# AMS_Enerdel_Adapter_rev7.net
KiCad netlist of a schematic drawn in EAGLE
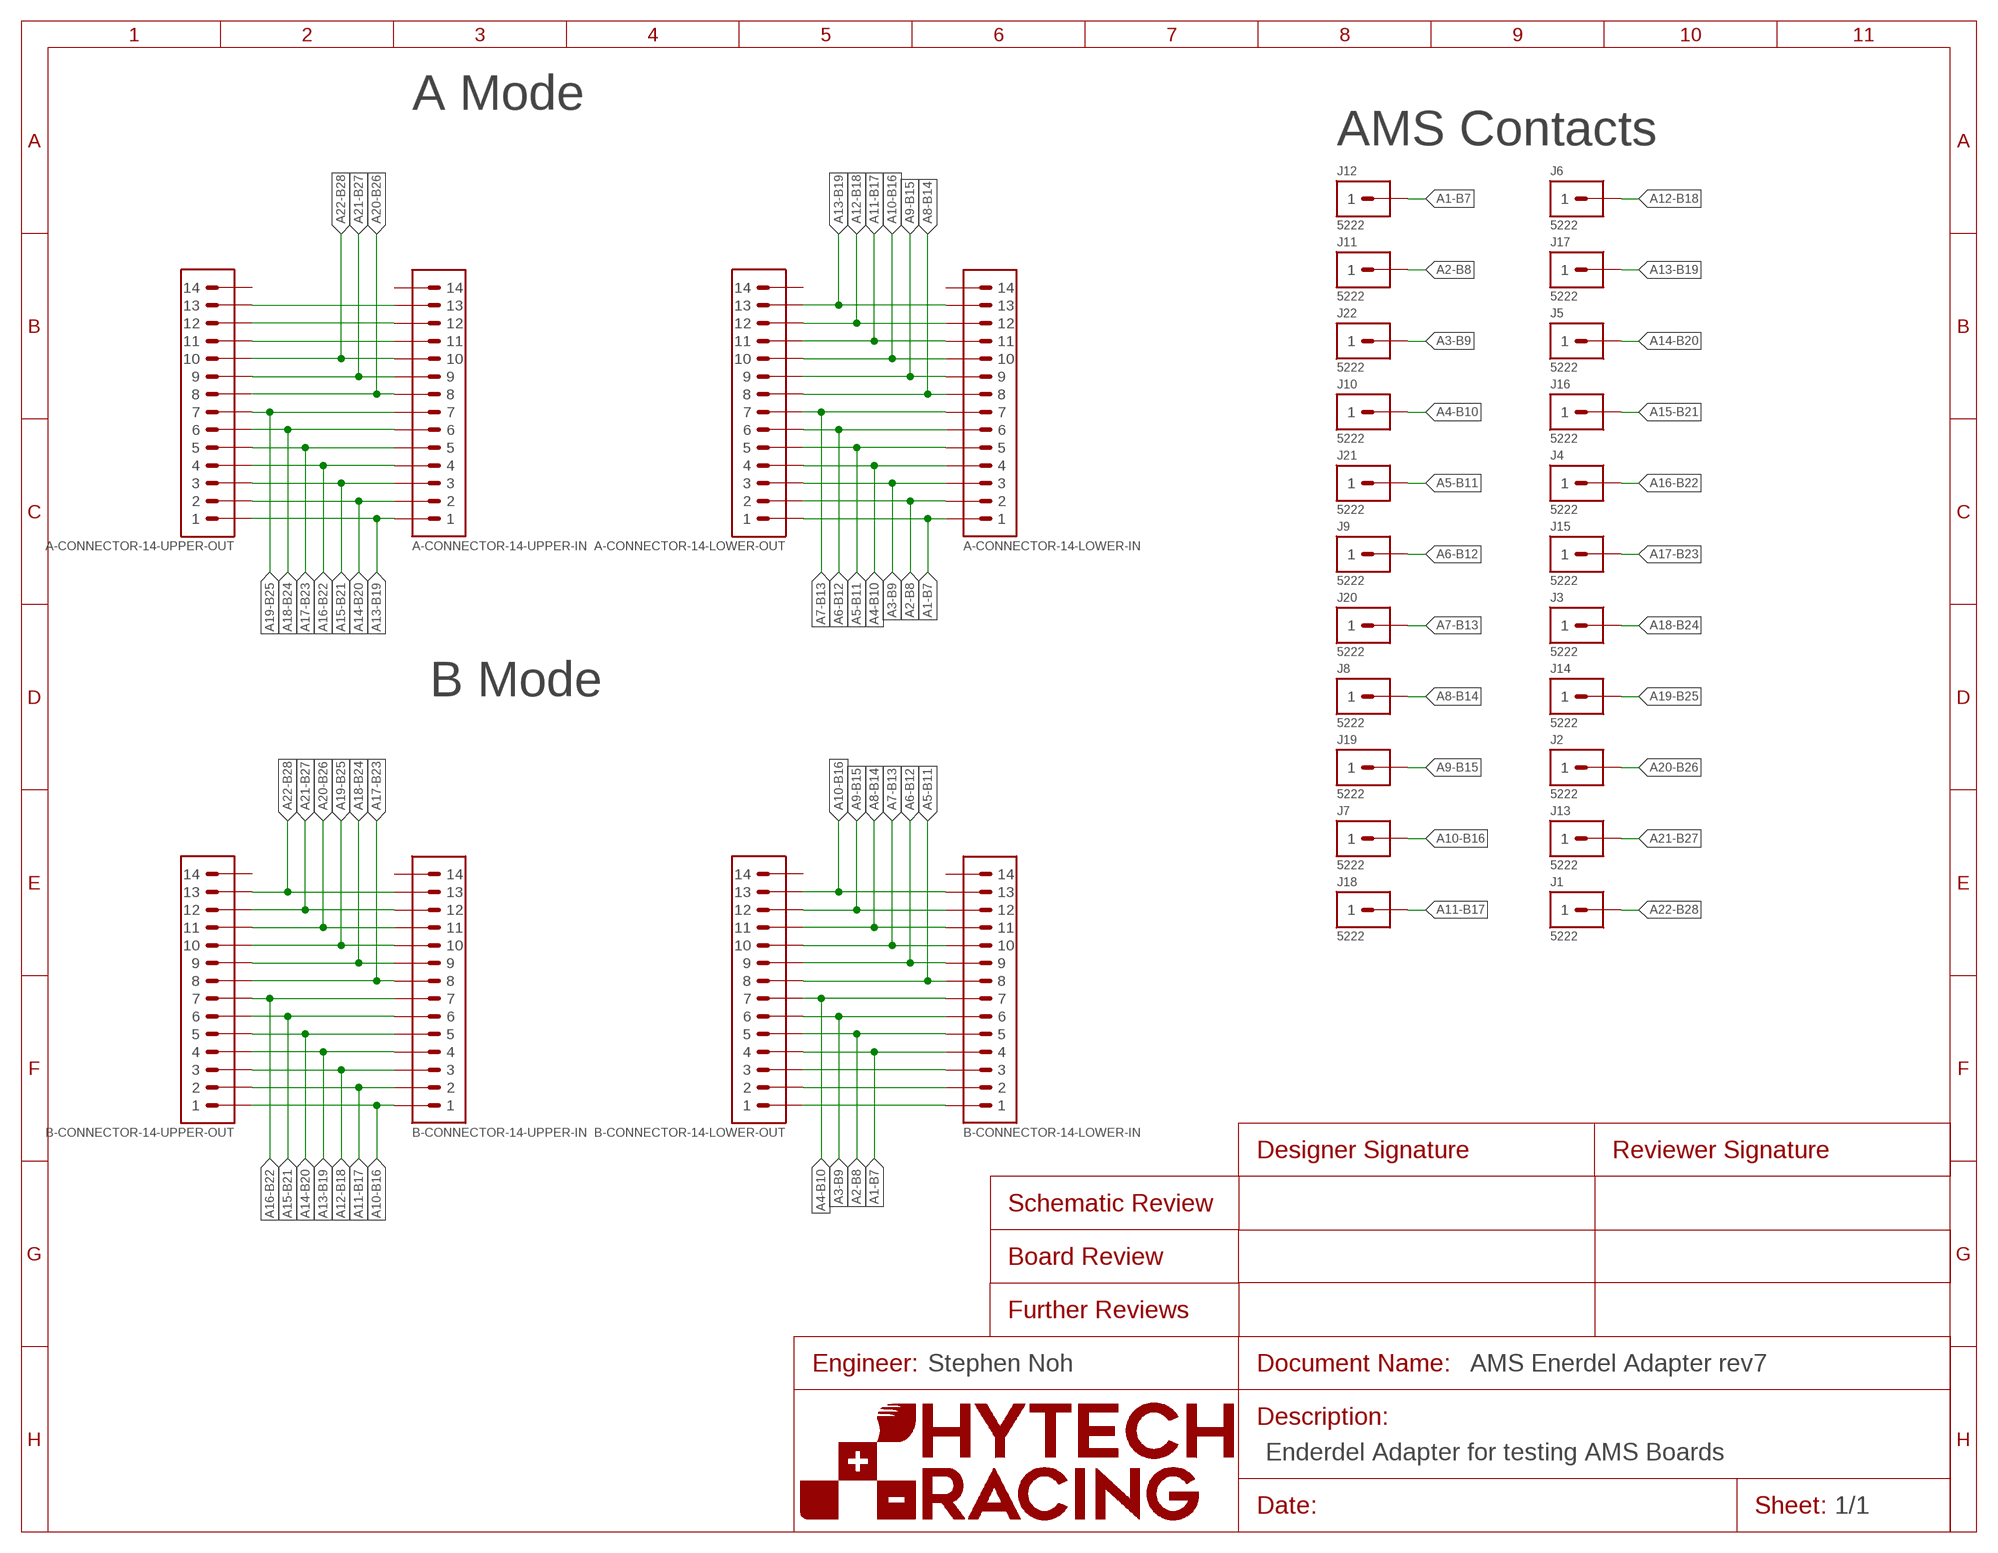
[diagram p0: schematic, sheet 1]

(export (version "E")
  (design (tool "Eeschema 10.0.6"))
  (components
    (comp (ref "A-CONNECTOR-14-LOWER-IN")
      (value "CONNECTOR-14_MINIFIT_")
      (footprint "eagle-import:MOLEX_MINIFIT_PTH_14")
      (libsource (lib "eagle-import") (part "CONNECTOR-14_?_MINIFIT"))
    )
    (comp (ref "A-CONNECTOR-14-LOWER-OUT")
      (value "CONNECTOR-14_MINIFIT_")
      (footprint "eagle-import:MOLEX_MINIFIT_PTH_14")
      (libsource (lib "eagle-import") (part "CONNECTOR-14_?_MINIFIT"))
    )
    (comp (ref "A-CONNECTOR-14-UPPER-IN")
      (value "CONNECTOR-14_NANOFIT_")
      (footprint "eagle-import:MOLEX_NANOFIT_PTH_14")
      (libsource (lib "eagle-import") (part "CONNECTOR-14_?_NANOFIT"))
    )
    (comp (ref "A-CONNECTOR-14-UPPER-OUT")
      (value "CONNECTOR-14_NANOFIT_")
      (footprint "eagle-import:MOLEX_NANOFIT_PTH_14")
      (libsource (lib "eagle-import") (part "CONNECTOR-14_?_NANOFIT"))
    )
    (comp (ref "B-CONNECTOR-14-LOWER-IN")
      (value "CONNECTOR-14_MINIFIT_")
      (footprint "eagle-import:MOLEX_MINIFIT_PTH_14")
      (libsource (lib "eagle-import") (part "CONNECTOR-14_?_MINIFIT"))
    )
    (comp (ref "B-CONNECTOR-14-LOWER-OUT")
      (value "CONNECTOR-14_MINIFIT_")
      (footprint "eagle-import:MOLEX_MINIFIT_PTH_14")
      (libsource (lib "eagle-import") (part "CONNECTOR-14_?_MINIFIT"))
    )
    (comp (ref "B-CONNECTOR-14-UPPER-IN")
      (value "CONNECTOR-14_NANOFIT_")
      (footprint "eagle-import:MOLEX_NANOFIT_PTH_14")
      (libsource (lib "eagle-import") (part "CONNECTOR-14_?_NANOFIT"))
    )
    (comp (ref "B-CONNECTOR-14-UPPER-OUT")
      (value "CONNECTOR-14_NANOFIT_")
      (footprint "eagle-import:MOLEX_NANOFIT_PTH_14")
      (libsource (lib "eagle-import") (part "CONNECTOR-14_?_NANOFIT"))
    )
    (comp (ref "J1")
      (value "CONNECTOR-1_5222_")
      (footprint "eagle-import:5222")
      (fields (field (name "MPN") "5222") (field (name "MANUFACTURER") "Keystone Electronics"))
      (libsource (lib "eagle-import") (part "CONNECTOR-1_?_5222"))
    )
    (comp (ref "J2")
      (value "CONNECTOR-1_5222_")
      (footprint "eagle-import:5222")
      (fields (field (name "MPN") "5222") (field (name "MANUFACTURER") "Keystone Electronics"))
      (libsource (lib "eagle-import") (part "CONNECTOR-1_?_5222"))
    )
    (comp (ref "J3")
      (value "CONNECTOR-1_5222_")
      (footprint "eagle-import:5222")
      (fields (field (name "MPN") "5222") (field (name "MANUFACTURER") "Keystone Electronics"))
      (libsource (lib "eagle-import") (part "CONNECTOR-1_?_5222"))
    )
    (comp (ref "J4")
      (value "CONNECTOR-1_5222_")
      (footprint "eagle-import:5222")
      (fields (field (name "MPN") "5222") (field (name "MANUFACTURER") "Keystone Electronics"))
      (libsource (lib "eagle-import") (part "CONNECTOR-1_?_5222"))
    )
    (comp (ref "J5")
      (value "CONNECTOR-1_5222_")
      (footprint "eagle-import:5222")
      (fields (field (name "MPN") "5222") (field (name "MANUFACTURER") "Keystone Electronics"))
      (libsource (lib "eagle-import") (part "CONNECTOR-1_?_5222"))
    )
    (comp (ref "J6")
      (value "CONNECTOR-1_5222_")
      (footprint "eagle-import:5222")
      (fields (field (name "MPN") "5222") (field (name "MANUFACTURER") "Keystone Electronics"))
      (libsource (lib "eagle-import") (part "CONNECTOR-1_?_5222"))
    )
    (comp (ref "J7")
      (value "CONNECTOR-1_5222_")
      (footprint "eagle-import:5222")
      (fields (field (name "MPN") "5222") (field (name "MANUFACTURER") "Keystone Electronics"))
      (libsource (lib "eagle-import") (part "CONNECTOR-1_?_5222"))
    )
    (comp (ref "J8")
      (value "CONNECTOR-1_5222_")
      (footprint "eagle-import:5222")
      (fields (field (name "MPN") "5222") (field (name "MANUFACTURER") "Keystone Electronics"))
      (libsource (lib "eagle-import") (part "CONNECTOR-1_?_5222"))
    )
    (comp (ref "J9")
      (value "CONNECTOR-1_5222_")
      (footprint "eagle-import:5222")
      (fields (field (name "MPN") "5222") (field (name "MANUFACTURER") "Keystone Electronics"))
      (libsource (lib "eagle-import") (part "CONNECTOR-1_?_5222"))
    )
    (comp (ref "J10")
      (value "CONNECTOR-1_5222_")
      (footprint "eagle-import:5222")
      (fields (field (name "MPN") "5222") (field (name "MANUFACTURER") "Keystone Electronics"))
      (libsource (lib "eagle-import") (part "CONNECTOR-1_?_5222"))
    )
    (comp (ref "J11")
      (value "CONNECTOR-1_5222_")
      (footprint "eagle-import:5222")
      (fields (field (name "MPN") "5222") (field (name "MANUFACTURER") "Keystone Electronics"))
      (libsource (lib "eagle-import") (part "CONNECTOR-1_?_5222"))
    )
    (comp (ref "J12")
      (value "CONNECTOR-1_5222_")
      (footprint "eagle-import:5222")
      (fields (field (name "MPN") "5222") (field (name "MANUFACTURER") "Keystone Electronics"))
      (libsource (lib "eagle-import") (part "CONNECTOR-1_?_5222"))
    )
    (comp (ref "J13")
      (value "CONNECTOR-1_5222_")
      (footprint "eagle-import:5222")
      (fields (field (name "MPN") "5222") (field (name "MANUFACTURER") "Keystone Electronics"))
      (libsource (lib "eagle-import") (part "CONNECTOR-1_?_5222"))
    )
    (comp (ref "J14")
      (value "CONNECTOR-1_5222_")
      (footprint "eagle-import:5222")
      (fields (field (name "MPN") "5222") (field (name "MANUFACTURER") "Keystone Electronics"))
      (libsource (lib "eagle-import") (part "CONNECTOR-1_?_5222"))
    )
    (comp (ref "J15")
      (value "CONNECTOR-1_5222_")
      (footprint "eagle-import:5222")
      (fields (field (name "MPN") "5222") (field (name "MANUFACTURER") "Keystone Electronics"))
      (libsource (lib "eagle-import") (part "CONNECTOR-1_?_5222"))
    )
    (comp (ref "J16")
      (value "CONNECTOR-1_5222_")
      (footprint "eagle-import:5222")
      (fields (field (name "MPN") "5222") (field (name "MANUFACTURER") "Keystone Electronics"))
      (libsource (lib "eagle-import") (part "CONNECTOR-1_?_5222"))
    )
    (comp (ref "J17")
      (value "CONNECTOR-1_5222_")
      (footprint "eagle-import:5222")
      (fields (field (name "MPN") "5222") (field (name "MANUFACTURER") "Keystone Electronics"))
      (libsource (lib "eagle-import") (part "CONNECTOR-1_?_5222"))
    )
    (comp (ref "J18")
      (value "CONNECTOR-1_5222_")
      (footprint "eagle-import:5222")
      (fields (field (name "MPN") "5222") (field (name "MANUFACTURER") "Keystone Electronics"))
      (libsource (lib "eagle-import") (part "CONNECTOR-1_?_5222"))
    )
    (comp (ref "J19")
      (value "CONNECTOR-1_5222_")
      (footprint "eagle-import:5222")
      (fields (field (name "MPN") "5222") (field (name "MANUFACTURER") "Keystone Electronics"))
      (libsource (lib "eagle-import") (part "CONNECTOR-1_?_5222"))
    )
    (comp (ref "J20")
      (value "CONNECTOR-1_5222_")
      (footprint "eagle-import:5222")
      (fields (field (name "MPN") "5222") (field (name "MANUFACTURER") "Keystone Electronics"))
      (libsource (lib "eagle-import") (part "CONNECTOR-1_?_5222"))
    )
    (comp (ref "J21")
      (value "CONNECTOR-1_5222_")
      (footprint "eagle-import:5222")
      (fields (field (name "MPN") "5222") (field (name "MANUFACTURER") "Keystone Electronics"))
      (libsource (lib "eagle-import") (part "CONNECTOR-1_?_5222"))
    )
    (comp (ref "J22")
      (value "CONNECTOR-1_5222_")
      (footprint "eagle-import:5222")
      (fields (field (name "MPN") "5222") (field (name "MANUFACTURER") "Keystone Electronics"))
      (libsource (lib "eagle-import") (part "CONNECTOR-1_?_5222"))
    )
  )
  (nets
    (net (code "1") (name "A1-B7") (class "Default")
      (node (ref "A-CONNECTOR-14-LOWER-IN") (pin "1") (pinfunction "1_1") (pintype "passive"))
      (node (ref "A-CONNECTOR-14-LOWER-OUT") (pin "1") (pinfunction "1_1") (pintype "passive"))
      (node (ref "B-CONNECTOR-14-LOWER-IN") (pin "4") (pinfunction "4_4") (pintype "passive"))
      (node (ref "B-CONNECTOR-14-LOWER-OUT") (pin "4") (pinfunction "4_4") (pintype "passive"))
      (node (ref "J12") (pin "1") (pinfunction "1_1") (pintype "passive"))
    )
    (net (code "2") (name "A2-B8") (class "Default")
      (node (ref "A-CONNECTOR-14-LOWER-IN") (pin "2") (pinfunction "2_2") (pintype "passive"))
      (node (ref "A-CONNECTOR-14-LOWER-OUT") (pin "2") (pinfunction "2_2") (pintype "passive"))
      (node (ref "B-CONNECTOR-14-LOWER-IN") (pin "5") (pinfunction "5_5") (pintype "passive"))
      (node (ref "B-CONNECTOR-14-LOWER-OUT") (pin "5") (pinfunction "5_5") (pintype "passive"))
      (node (ref "J11") (pin "1") (pinfunction "1_1") (pintype "passive"))
    )
    (net (code "3") (name "A3-B9") (class "Default")
      (node (ref "A-CONNECTOR-14-LOWER-IN") (pin "3") (pinfunction "3_3") (pintype "passive"))
      (node (ref "A-CONNECTOR-14-LOWER-OUT") (pin "3") (pinfunction "3_3") (pintype "passive"))
      (node (ref "B-CONNECTOR-14-LOWER-IN") (pin "6") (pinfunction "6_6") (pintype "passive"))
      (node (ref "B-CONNECTOR-14-LOWER-OUT") (pin "6") (pinfunction "6_6") (pintype "passive"))
      (node (ref "J22") (pin "1") (pinfunction "1_1") (pintype "passive"))
    )
    (net (code "4") (name "A4-B10") (class "Default")
      (node (ref "A-CONNECTOR-14-LOWER-IN") (pin "4") (pinfunction "4_4") (pintype "passive"))
      (node (ref "A-CONNECTOR-14-LOWER-OUT") (pin "4") (pinfunction "4_4") (pintype "passive"))
      (node (ref "B-CONNECTOR-14-LOWER-IN") (pin "7") (pinfunction "7_7") (pintype "passive"))
      (node (ref "B-CONNECTOR-14-LOWER-OUT") (pin "7") (pinfunction "7_7") (pintype "passive"))
      (node (ref "J10") (pin "1") (pinfunction "1_1") (pintype "passive"))
    )
    (net (code "5") (name "A5-B11") (class "Default")
      (node (ref "A-CONNECTOR-14-LOWER-IN") (pin "5") (pinfunction "5_5") (pintype "passive"))
      (node (ref "A-CONNECTOR-14-LOWER-OUT") (pin "5") (pinfunction "5_5") (pintype "passive"))
      (node (ref "B-CONNECTOR-14-LOWER-IN") (pin "8") (pinfunction "8_8") (pintype "passive"))
      (node (ref "B-CONNECTOR-14-LOWER-OUT") (pin "8") (pinfunction "8_8") (pintype "passive"))
      (node (ref "J21") (pin "1") (pinfunction "1_1") (pintype "passive"))
    )
    (net (code "6") (name "A6-B12") (class "Default")
      (node (ref "A-CONNECTOR-14-LOWER-IN") (pin "6") (pinfunction "6_6") (pintype "passive"))
      (node (ref "A-CONNECTOR-14-LOWER-OUT") (pin "6") (pinfunction "6_6") (pintype "passive"))
      (node (ref "B-CONNECTOR-14-LOWER-IN") (pin "9") (pinfunction "9_9") (pintype "passive"))
      (node (ref "B-CONNECTOR-14-LOWER-OUT") (pin "9") (pinfunction "9_9") (pintype "passive"))
      (node (ref "J9") (pin "1") (pinfunction "1_1") (pintype "passive"))
    )
    (net (code "7") (name "A7-B13") (class "Default")
      (node (ref "A-CONNECTOR-14-LOWER-IN") (pin "7") (pinfunction "7_7") (pintype "passive"))
      (node (ref "A-CONNECTOR-14-LOWER-OUT") (pin "7") (pinfunction "7_7") (pintype "passive"))
      (node (ref "B-CONNECTOR-14-LOWER-IN") (pin "10") (pinfunction "10_10") (pintype "passive"))
      (node (ref "B-CONNECTOR-14-LOWER-OUT") (pin "10") (pinfunction "10_10") (pintype "passive"))
      (node (ref "J20") (pin "1") (pinfunction "1_1") (pintype "passive"))
    )
    (net (code "8") (name "A8-B14") (class "Default")
      (node (ref "A-CONNECTOR-14-LOWER-IN") (pin "8") (pinfunction "8_8") (pintype "passive"))
      (node (ref "A-CONNECTOR-14-LOWER-OUT") (pin "8") (pinfunction "8_8") (pintype "passive"))
      (node (ref "B-CONNECTOR-14-LOWER-IN") (pin "11") (pinfunction "11_11") (pintype "passive"))
      (node (ref "B-CONNECTOR-14-LOWER-OUT") (pin "11") (pinfunction "11_11") (pintype "passive"))
      (node (ref "J8") (pin "1") (pinfunction "1_1") (pintype "passive"))
    )
    (net (code "9") (name "A9-B15") (class "Default")
      (node (ref "A-CONNECTOR-14-LOWER-IN") (pin "9") (pinfunction "9_9") (pintype "passive"))
      (node (ref "A-CONNECTOR-14-LOWER-OUT") (pin "9") (pinfunction "9_9") (pintype "passive"))
      (node (ref "B-CONNECTOR-14-LOWER-IN") (pin "12") (pinfunction "12_12") (pintype "passive"))
      (node (ref "B-CONNECTOR-14-LOWER-OUT") (pin "12") (pinfunction "12_12") (pintype "passive"))
      (node (ref "J19") (pin "1") (pinfunction "1_1") (pintype "passive"))
    )
    (net (code "10") (name "A10-B16") (class "Default")
      (node (ref "A-CONNECTOR-14-LOWER-IN") (pin "10") (pinfunction "10_10") (pintype "passive"))
      (node (ref "A-CONNECTOR-14-LOWER-OUT") (pin "10") (pinfunction "10_10") (pintype "passive"))
      (node (ref "B-CONNECTOR-14-LOWER-IN") (pin "13") (pinfunction "13_13") (pintype "passive"))
      (node (ref "B-CONNECTOR-14-LOWER-OUT") (pin "13") (pinfunction "13_13") (pintype "passive"))
      (node (ref "B-CONNECTOR-14-UPPER-IN") (pin "1") (pinfunction "1_1") (pintype "passive"))
      (node (ref "B-CONNECTOR-14-UPPER-OUT") (pin "1") (pinfunction "1_1") (pintype "passive"))
      (node (ref "J7") (pin "1") (pinfunction "1_1") (pintype "passive"))
    )
    (net (code "11") (name "A11-B17") (class "Default")
      (node (ref "A-CONNECTOR-14-LOWER-IN") (pin "11") (pinfunction "11_11") (pintype "passive"))
      (node (ref "A-CONNECTOR-14-LOWER-OUT") (pin "11") (pinfunction "11_11") (pintype "passive"))
      (node (ref "B-CONNECTOR-14-UPPER-IN") (pin "2") (pinfunction "2_2") (pintype "passive"))
      (node (ref "B-CONNECTOR-14-UPPER-OUT") (pin "2") (pinfunction "2_2") (pintype "passive"))
      (node (ref "J18") (pin "1") (pinfunction "1_1") (pintype "passive"))
    )
    (net (code "12") (name "A12-B18") (class "Default")
      (node (ref "A-CONNECTOR-14-LOWER-IN") (pin "12") (pinfunction "12_12") (pintype "passive"))
      (node (ref "A-CONNECTOR-14-LOWER-OUT") (pin "12") (pinfunction "12_12") (pintype "passive"))
      (node (ref "B-CONNECTOR-14-UPPER-IN") (pin "3") (pinfunction "3_3") (pintype "passive"))
      (node (ref "B-CONNECTOR-14-UPPER-OUT") (pin "3") (pinfunction "3_3") (pintype "passive"))
      (node (ref "J6") (pin "1") (pinfunction "1_1") (pintype "passive"))
    )
    (net (code "13") (name "A13-B19") (class "Default")
      (node (ref "A-CONNECTOR-14-LOWER-IN") (pin "13") (pinfunction "13_13") (pintype "passive"))
      (node (ref "A-CONNECTOR-14-LOWER-OUT") (pin "13") (pinfunction "13_13") (pintype "passive"))
      (node (ref "A-CONNECTOR-14-UPPER-IN") (pin "1") (pinfunction "1_1") (pintype "passive"))
      (node (ref "A-CONNECTOR-14-UPPER-OUT") (pin "1") (pinfunction "1_1") (pintype "passive"))
      (node (ref "B-CONNECTOR-14-UPPER-IN") (pin "4") (pinfunction "4_4") (pintype "passive"))
      (node (ref "B-CONNECTOR-14-UPPER-OUT") (pin "4") (pinfunction "4_4") (pintype "passive"))
      (node (ref "J17") (pin "1") (pinfunction "1_1") (pintype "passive"))
    )
    (net (code "14") (name "A14-B20") (class "Default")
      (node (ref "A-CONNECTOR-14-UPPER-IN") (pin "2") (pinfunction "2_2") (pintype "passive"))
      (node (ref "A-CONNECTOR-14-UPPER-OUT") (pin "2") (pinfunction "2_2") (pintype "passive"))
      (node (ref "B-CONNECTOR-14-UPPER-IN") (pin "5") (pinfunction "5_5") (pintype "passive"))
      (node (ref "B-CONNECTOR-14-UPPER-OUT") (pin "5") (pinfunction "5_5") (pintype "passive"))
      (node (ref "J5") (pin "1") (pinfunction "1_1") (pintype "passive"))
    )
    (net (code "15") (name "A15-B21") (class "Default")
      (node (ref "A-CONNECTOR-14-UPPER-IN") (pin "3") (pinfunction "3_3") (pintype "passive"))
      (node (ref "A-CONNECTOR-14-UPPER-OUT") (pin "3") (pinfunction "3_3") (pintype "passive"))
      (node (ref "B-CONNECTOR-14-UPPER-IN") (pin "6") (pinfunction "6_6") (pintype "passive"))
      (node (ref "B-CONNECTOR-14-UPPER-OUT") (pin "6") (pinfunction "6_6") (pintype "passive"))
      (node (ref "J16") (pin "1") (pinfunction "1_1") (pintype "passive"))
    )
    (net (code "16") (name "A16-B22") (class "Default")
      (node (ref "A-CONNECTOR-14-UPPER-IN") (pin "4") (pinfunction "4_4") (pintype "passive"))
      (node (ref "A-CONNECTOR-14-UPPER-OUT") (pin "4") (pinfunction "4_4") (pintype "passive"))
      (node (ref "B-CONNECTOR-14-UPPER-IN") (pin "7") (pinfunction "7_7") (pintype "passive"))
      (node (ref "B-CONNECTOR-14-UPPER-OUT") (pin "7") (pinfunction "7_7") (pintype "passive"))
      (node (ref "J4") (pin "1") (pinfunction "1_1") (pintype "passive"))
    )
    (net (code "17") (name "A17-B23") (class "Default")
      (node (ref "A-CONNECTOR-14-UPPER-IN") (pin "5") (pinfunction "5_5") (pintype "passive"))
      (node (ref "A-CONNECTOR-14-UPPER-OUT") (pin "5") (pinfunction "5_5") (pintype "passive"))
      (node (ref "B-CONNECTOR-14-UPPER-IN") (pin "8") (pinfunction "8_8") (pintype "passive"))
      (node (ref "B-CONNECTOR-14-UPPER-OUT") (pin "8") (pinfunction "8_8") (pintype "passive"))
      (node (ref "J15") (pin "1") (pinfunction "1_1") (pintype "passive"))
    )
    (net (code "18") (name "A18-B24") (class "Default")
      (node (ref "A-CONNECTOR-14-UPPER-IN") (pin "6") (pinfunction "6_6") (pintype "passive"))
      (node (ref "A-CONNECTOR-14-UPPER-OUT") (pin "6") (pinfunction "6_6") (pintype "passive"))
      (node (ref "B-CONNECTOR-14-UPPER-IN") (pin "9") (pinfunction "9_9") (pintype "passive"))
      (node (ref "B-CONNECTOR-14-UPPER-OUT") (pin "9") (pinfunction "9_9") (pintype "passive"))
      (node (ref "J3") (pin "1") (pinfunction "1_1") (pintype "passive"))
    )
    (net (code "19") (name "A19-B25") (class "Default")
      (node (ref "A-CONNECTOR-14-UPPER-IN") (pin "7") (pinfunction "7_7") (pintype "passive"))
      (node (ref "A-CONNECTOR-14-UPPER-OUT") (pin "7") (pinfunction "7_7") (pintype "passive"))
      (node (ref "B-CONNECTOR-14-UPPER-IN") (pin "10") (pinfunction "10_10") (pintype "passive"))
      (node (ref "B-CONNECTOR-14-UPPER-OUT") (pin "10") (pinfunction "10_10") (pintype "passive"))
      (node (ref "J14") (pin "1") (pinfunction "1_1") (pintype "passive"))
    )
    (net (code "20") (name "A20-B26") (class "Default")
      (node (ref "A-CONNECTOR-14-UPPER-IN") (pin "8") (pinfunction "8_8") (pintype "passive"))
      (node (ref "A-CONNECTOR-14-UPPER-OUT") (pin "8") (pinfunction "8_8") (pintype "passive"))
      (node (ref "B-CONNECTOR-14-UPPER-IN") (pin "11") (pinfunction "11_11") (pintype "passive"))
      (node (ref "B-CONNECTOR-14-UPPER-OUT") (pin "11") (pinfunction "11_11") (pintype "passive"))
      (node (ref "J2") (pin "1") (pinfunction "1_1") (pintype "passive"))
    )
    (net (code "21") (name "A21-B27") (class "Default")
      (node (ref "A-CONNECTOR-14-UPPER-IN") (pin "9") (pinfunction "9_9") (pintype "passive"))
      (node (ref "A-CONNECTOR-14-UPPER-OUT") (pin "9") (pinfunction "9_9") (pintype "passive"))
      (node (ref "B-CONNECTOR-14-UPPER-IN") (pin "12") (pinfunction "12_12") (pintype "passive"))
      (node (ref "B-CONNECTOR-14-UPPER-OUT") (pin "12") (pinfunction "12_12") (pintype "passive"))
      (node (ref "J13") (pin "1") (pinfunction "1_1") (pintype "passive"))
    )
    (net (code "22") (name "A22-B28") (class "Default")
      (node (ref "A-CONNECTOR-14-UPPER-IN") (pin "10") (pinfunction "10_10") (pintype "passive"))
      (node (ref "A-CONNECTOR-14-UPPER-OUT") (pin "10") (pinfunction "10_10") (pintype "passive"))
      (node (ref "B-CONNECTOR-14-UPPER-IN") (pin "13") (pinfunction "13_13") (pintype "passive"))
      (node (ref "B-CONNECTOR-14-UPPER-OUT") (pin "13") (pinfunction "13_13") (pintype "passive"))
      (node (ref "J1") (pin "1") (pinfunction "1_1") (pintype "passive"))
    )
    (net (code "23") (name "Net-(A-CONNECTOR-14-UPPER-IN-Pad11)") (class "Default")
      (node (ref "A-CONNECTOR-14-UPPER-IN") (pin "11") (pinfunction "11_11") (pintype "passive"))
      (node (ref "A-CONNECTOR-14-UPPER-OUT") (pin "11") (pinfunction "11_11") (pintype "passive"))
    )
    (net (code "24") (name "Net-(A-CONNECTOR-14-UPPER-IN-Pad12)") (class "Default")
      (node (ref "A-CONNECTOR-14-UPPER-IN") (pin "12") (pinfunction "12_12") (pintype "passive"))
      (node (ref "A-CONNECTOR-14-UPPER-OUT") (pin "12") (pinfunction "12_12") (pintype "passive"))
    )
    (net (code "25") (name "Net-(A-CONNECTOR-14-UPPER-IN-Pad13)") (class "Default")
      (node (ref "A-CONNECTOR-14-UPPER-IN") (pin "13") (pinfunction "13_13") (pintype "passive"))
      (node (ref "A-CONNECTOR-14-UPPER-OUT") (pin "13") (pinfunction "13_13") (pintype "passive"))
    )
    (net (code "26") (name "Net-(B-CONNECTOR-14-LOWER-IN-Pad1)") (class "Default")
      (node (ref "B-CONNECTOR-14-LOWER-IN") (pin "1") (pinfunction "1_1") (pintype "passive"))
      (node (ref "B-CONNECTOR-14-LOWER-OUT") (pin "1") (pinfunction "1_1") (pintype "passive"))
    )
    (net (code "27") (name "Net-(B-CONNECTOR-14-LOWER-IN-Pad2)") (class "Default")
      (node (ref "B-CONNECTOR-14-LOWER-IN") (pin "2") (pinfunction "2_2") (pintype "passive"))
      (node (ref "B-CONNECTOR-14-LOWER-OUT") (pin "2") (pinfunction "2_2") (pintype "passive"))
    )
    (net (code "28") (name "Net-(B-CONNECTOR-14-LOWER-IN-Pad3)") (class "Default")
      (node (ref "B-CONNECTOR-14-LOWER-IN") (pin "3") (pinfunction "3_3") (pintype "passive"))
      (node (ref "B-CONNECTOR-14-LOWER-OUT") (pin "3") (pinfunction "3_3") (pintype "passive"))
    )
    (net (code "29") (name "unconnected-(A-CONNECTOR-14-LOWER-IN-Pad14)") (class "Default")
      (node (ref "A-CONNECTOR-14-LOWER-IN") (pin "14") (pinfunction "14_14") (pintype "passive"))
    )
    (net (code "30") (name "unconnected-(A-CONNECTOR-14-LOWER-OUT-Pad14)") (class "Default")
      (node (ref "A-CONNECTOR-14-LOWER-OUT") (pin "14") (pinfunction "14_14") (pintype "passive"))
    )
    (net (code "31") (name "unconnected-(A-CONNECTOR-14-UPPER-IN-Pad14)") (class "Default")
      (node (ref "A-CONNECTOR-14-UPPER-IN") (pin "14") (pinfunction "14_14") (pintype "passive"))
    )
    (net (code "32") (name "unconnected-(A-CONNECTOR-14-UPPER-OUT-Pad14)") (class "Default")
      (node (ref "A-CONNECTOR-14-UPPER-OUT") (pin "14") (pinfunction "14_14") (pintype "passive"))
    )
    (net (code "33") (name "unconnected-(B-CONNECTOR-14-LOWER-IN-Pad14)") (class "Default")
      (node (ref "B-CONNECTOR-14-LOWER-IN") (pin "14") (pinfunction "14_14") (pintype "passive"))
    )
    (net (code "34") (name "unconnected-(B-CONNECTOR-14-LOWER-OUT-Pad14)") (class "Default")
      (node (ref "B-CONNECTOR-14-LOWER-OUT") (pin "14") (pinfunction "14_14") (pintype "passive"))
    )
    (net (code "35") (name "unconnected-(B-CONNECTOR-14-UPPER-IN-Pad14)") (class "Default")
      (node (ref "B-CONNECTOR-14-UPPER-IN") (pin "14") (pinfunction "14_14") (pintype "passive"))
    )
    (net (code "36") (name "unconnected-(B-CONNECTOR-14-UPPER-OUT-Pad14)") (class "Default")
      (node (ref "B-CONNECTOR-14-UPPER-OUT") (pin "14") (pinfunction "14_14") (pintype "passive"))
    )
  )
)
